# Display.net
KiCad netlist of a schematic drawn in Altium Designer
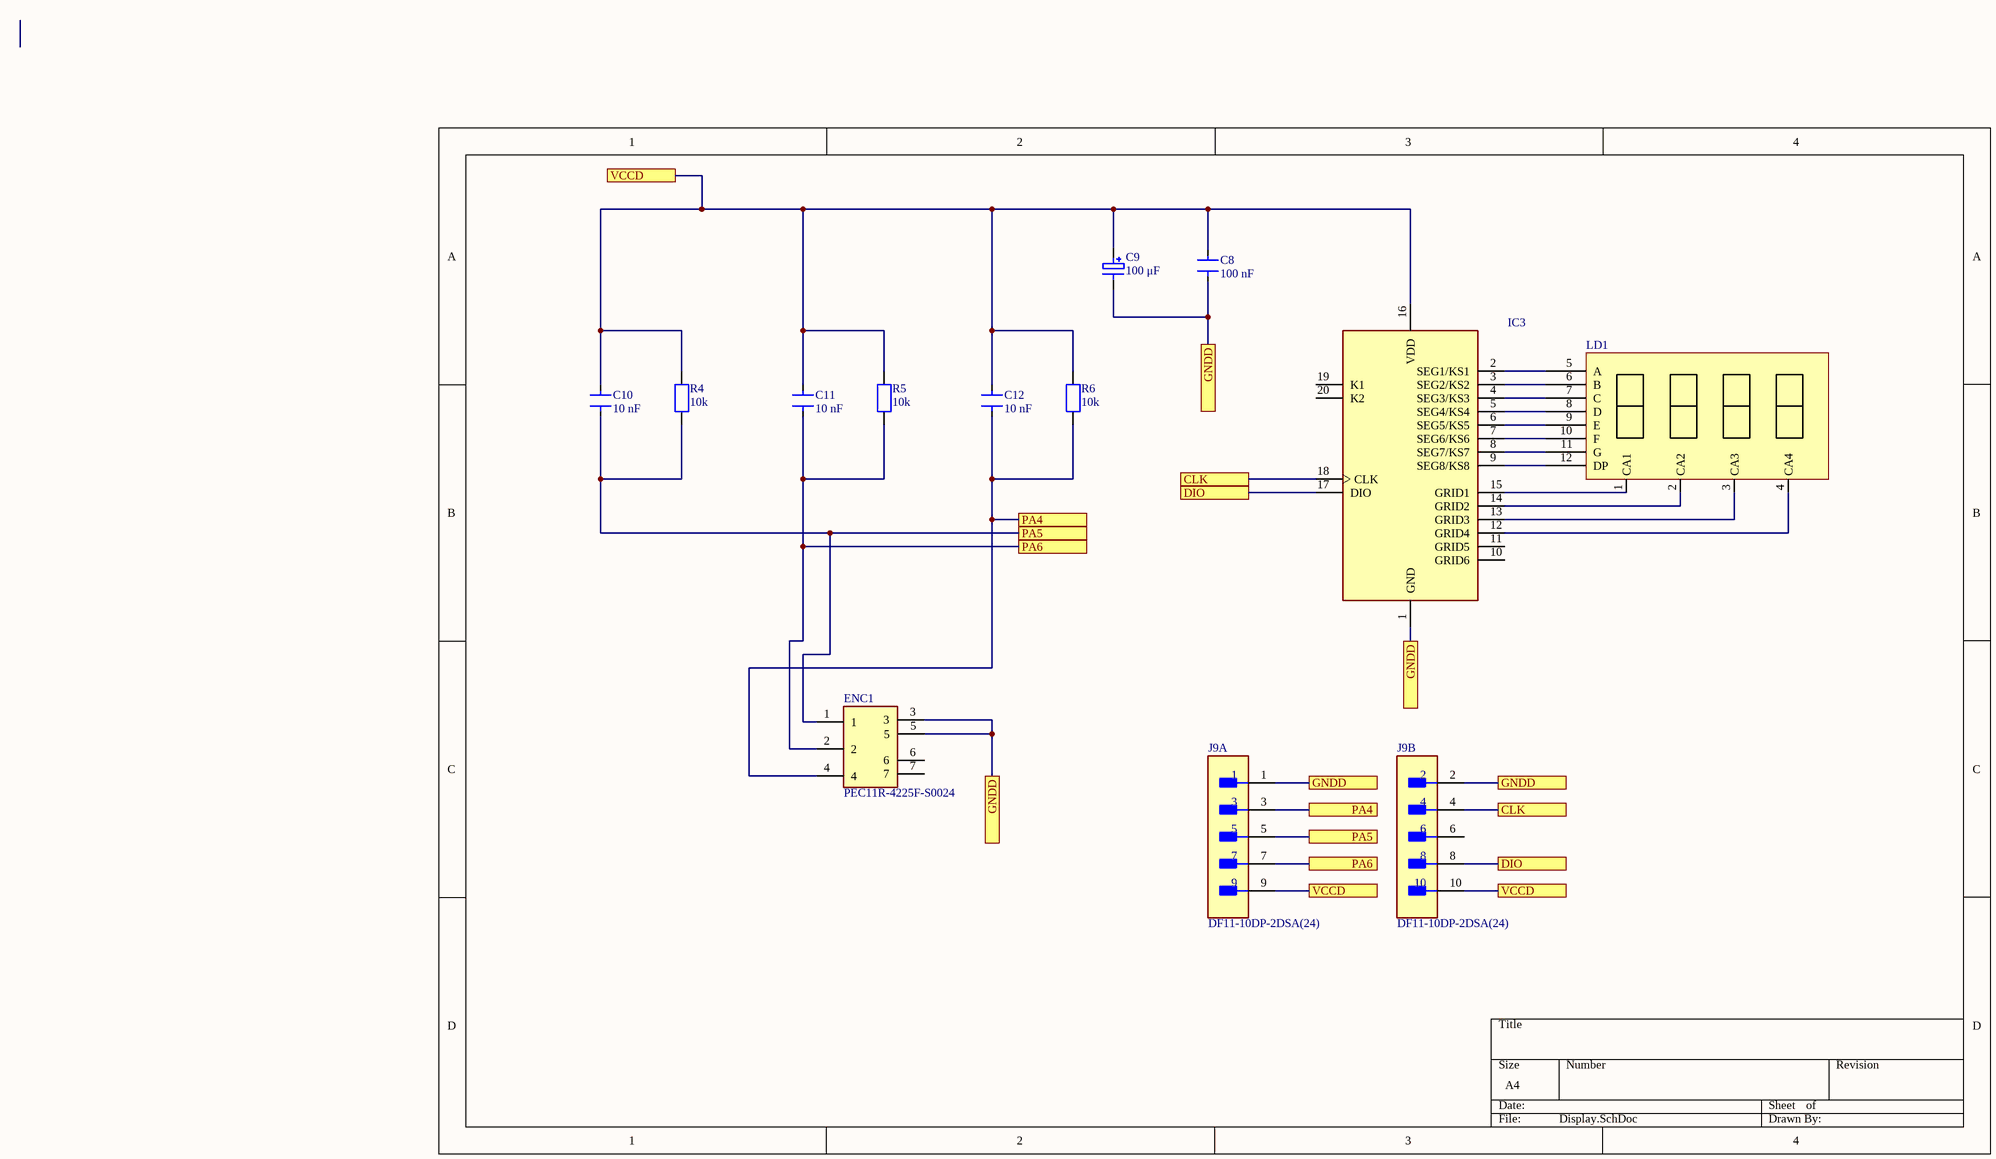
[diagram p0: Display.SchDoc]

(export (version "E")
  (design (tool "Eeschema 10.0.6"))
  (components
    (comp (ref "C8")
      (value "100 nF")
      (footprint "0805")
      (description "Chip Multilayer Ceramic Capacitors for General Purpose, 0805, 10uF, X5R, 15%, 10%, 25V")
      (fields (field (name "VOLTAGE") "25V") (field (name "TOLERANCE") "10%"))
      (libsource (lib "Soldeerstation") (part "Condensator 0805"))
    )
    (comp (ref "C9")
      (value "100 μF")
      (footprint "Elco 100uF 25V")
      (fields
        (field (name "PART NUMBER") "02015A270JAT2A")
        (field (name "MANUFACTURER") "AVX Interconnect / Elco")
      )
      (libsource (lib "Soldeerstation") (part "Condensator Elco"))
    )
    (comp (ref "C10")
      (value "10 nF")
      (footprint "0805")
      (description "Chip Multilayer Ceramic Capacitors for General Purpose, 0805, 10uF, X5R, 15%, 10%, 25V")
      (fields (field (name "VOLTAGE") "25V") (field (name "TOLERANCE") "10%"))
      (libsource (lib "Soldeerstation") (part "Condensator 0805"))
    )
    (comp (ref "C11")
      (value "10 nF")
      (footprint "0805")
      (description "Chip Multilayer Ceramic Capacitors for General Purpose, 0805, 10uF, X5R, 15%, 10%, 25V")
      (fields (field (name "VOLTAGE") "25V") (field (name "TOLERANCE") "10%"))
      (libsource (lib "Soldeerstation") (part "Condensator 0805"))
    )
    (comp (ref "C12")
      (value "10 nF")
      (footprint "0805")
      (description "Chip Multilayer Ceramic Capacitors for General Purpose, 0805, 10uF, X5R, 15%, 10%, 25V")
      (fields (field (name "VOLTAGE") "25V") (field (name "TOLERANCE") "10%"))
      (libsource (lib "Soldeerstation") (part "Condensator 0805"))
    )
    (comp (ref "ENC1")
      (value "PEC11R-4225F-S0024")
      (footprint "Encoder")
      (description "Undefined or Miscellaneous")
      (fields (field (name "MOUSER2 PART NUMBER") "652-PEC11R-4225F-S24"))
      (libsource (lib "Soldeerstation") (part "Encoder"))
    )
    (comp (ref "IC3")
      (value "TM1637")
      (footprint "TM1637")
      (description "LED Drive Control Special Circuit")
      (fields (field (name "MF") "Titan Micro Electronics"))
      (libsource (lib "Soldeerstation") (part "TM1637"))
    )
    (comp (ref "J9")
      (value "DF11-10DP-2DSA(24)")
      (footprint "FP-DF11-10DP-2DSA_24-MFG")
      (description "CONN HEADER VERT 10POS 2MM")
      (fields
        (field (name "OCTOPART") "https://octopart.com/df11-10dp-2dsa%2824%29-hirose-39521433")
        (field (name "MANUFACTURER") "Hirose")
      )
      (libsource (lib "Soldeerstation") (part "CMP-11610-000008-1"))
    )
    (comp (ref "LD1")
      (value "7segment")
      (footprint "7segment")
      (libsource (lib "Soldeerstation") (part "7segment"))
    )
    (comp (ref "R4")
      (value "10k")
      (footprint "Resistor")
      (description "Resistor")
      (fields (field (name "MANUFACTURER") "Vishay Dale") (field (name "PART NUMBER") "CRCW08050000Z0EA"))
      (libsource (lib "Soldeerstation") (part "Resistor"))
    )
    (comp (ref "R5")
      (value "10k")
      (footprint "Resistor")
      (description "Resistor")
      (fields (field (name "MANUFACTURER") "Vishay Dale") (field (name "PART NUMBER") "CRCW08050000Z0EA"))
      (libsource (lib "Soldeerstation") (part "Resistor"))
    )
    (comp (ref "R6")
      (value "10k")
      (footprint "Resistor")
      (description "Resistor")
      (fields (field (name "MANUFACTURER") "Vishay Dale") (field (name "PART NUMBER") "CRCW08050000Z0EA"))
      (libsource (lib "Soldeerstation") (part "Resistor"))
    )
  )
  (nets
    (net (code "1") (name "/CLK") (class "Default")
      (node (ref "IC3") (pin "18") (pinfunction "CLK_18") (pintype "passive"))
      (node (ref "J9") (pin "4") (pinfunction "4_4") (pintype "passive"))
    )
    (net (code "2") (name "/DIO") (class "Default")
      (node (ref "IC3") (pin "17") (pinfunction "DIO_17") (pintype "passive"))
      (node (ref "J9") (pin "8") (pinfunction "8_8") (pintype "passive"))
    )
    (net (code "3") (name "/GNDD") (class "Default")
      (node (ref "C8") (pin "1") (pinfunction "1_1") (pintype "passive"))
      (node (ref "C9") (pin "2") (pinfunction "2_2") (pintype "passive"))
      (node (ref "ENC1") (pin "3") (pinfunction "3_3") (pintype "passive"))
      (node (ref "ENC1") (pin "5") (pinfunction "5_5") (pintype "passive"))
      (node (ref "IC3") (pin "1") (pinfunction "GND_1") (pintype "power_in"))
      (node (ref "J9") (pin "1") (pinfunction "1_1") (pintype "passive"))
      (node (ref "J9") (pin "2") (pinfunction "2_2") (pintype "passive"))
    )
    (net (code "4") (name "/PA4") (class "Default")
      (node (ref "C12") (pin "1") (pinfunction "1_1") (pintype "passive"))
      (node (ref "ENC1") (pin "4") (pinfunction "4_4") (pintype "passive"))
      (node (ref "J9") (pin "3") (pinfunction "3_3") (pintype "passive"))
      (node (ref "R6") (pin "1") (pintype "passive"))
    )
    (net (code "5") (name "/PA5") (class "Default")
      (node (ref "C10") (pin "1") (pinfunction "1_1") (pintype "passive"))
      (node (ref "ENC1") (pin "1") (pinfunction "1_1") (pintype "passive"))
      (node (ref "J9") (pin "5") (pinfunction "5_5") (pintype "passive"))
      (node (ref "R4") (pin "1") (pintype "passive"))
    )
    (net (code "6") (name "/PA6") (class "Default")
      (node (ref "C11") (pin "1") (pinfunction "1_1") (pintype "passive"))
      (node (ref "ENC1") (pin "2") (pinfunction "2_2") (pintype "passive"))
      (node (ref "J9") (pin "7") (pinfunction "7_7") (pintype "passive"))
      (node (ref "R5") (pin "1") (pintype "passive"))
    )
    (net (code "7") (name "/VCCD") (class "Default")
      (node (ref "C10") (pin "2") (pinfunction "2_2") (pintype "passive"))
      (node (ref "C11") (pin "2") (pinfunction "2_2") (pintype "passive"))
      (node (ref "C12") (pin "2") (pinfunction "2_2") (pintype "passive"))
      (node (ref "C8") (pin "2") (pinfunction "2_2") (pintype "passive"))
      (node (ref "C9") (pin "1") (pinfunction "1_1") (pintype "passive"))
      (node (ref "IC3") (pin "16") (pinfunction "VDD_16") (pintype "power_in"))
      (node (ref "J9") (pin "10") (pinfunction "10_10") (pintype "passive"))
      (node (ref "J9") (pin "9") (pinfunction "9_9") (pintype "passive"))
      (node (ref "R4") (pin "2") (pinfunction "2_2") (pintype "passive"))
      (node (ref "R5") (pin "2") (pinfunction "2_2") (pintype "passive"))
      (node (ref "R6") (pin "2") (pinfunction "2_2") (pintype "passive"))
    )
    (net (code "8") (name "Net-(IC3-GRID1)") (class "Default")
      (node (ref "IC3") (pin "15") (pinfunction "GRID1_15") (pintype "passive"))
      (node (ref "LD1") (pin "1") (pinfunction "CA1_1") (pintype "power_in"))
    )
    (net (code "9") (name "Net-(IC3-GRID2)") (class "Default")
      (node (ref "IC3") (pin "14") (pinfunction "GRID2_14") (pintype "passive"))
      (node (ref "LD1") (pin "2") (pinfunction "CA2_2") (pintype "power_in"))
    )
    (net (code "10") (name "Net-(IC3-GRID3)") (class "Default")
      (node (ref "IC3") (pin "13") (pinfunction "GRID3_13") (pintype "passive"))
      (node (ref "LD1") (pin "3") (pinfunction "CA3_3") (pintype "power_in"))
    )
    (net (code "11") (name "Net-(IC3-GRID4)") (class "Default")
      (node (ref "IC3") (pin "12") (pinfunction "GRID4_12") (pintype "passive"))
      (node (ref "LD1") (pin "4") (pinfunction "CA4_4") (pintype "power_in"))
    )
    (net (code "12") (name "Net-(IC3-SEG1{slash}KS1)") (class "Default")
      (node (ref "IC3") (pin "2") (pinfunction "SEG1/KS1_2") (pintype "passive"))
      (node (ref "LD1") (pin "5") (pinfunction "A_5") (pintype "passive"))
    )
    (net (code "13") (name "Net-(IC3-SEG2{slash}KS2)") (class "Default")
      (node (ref "IC3") (pin "3") (pinfunction "SEG2/KS2_3") (pintype "passive"))
      (node (ref "LD1") (pin "6") (pinfunction "B_6") (pintype "passive"))
    )
    (net (code "14") (name "Net-(IC3-SEG3{slash}KS3)") (class "Default")
      (node (ref "IC3") (pin "4") (pinfunction "SEG3/KS3_4") (pintype "passive"))
      (node (ref "LD1") (pin "7") (pinfunction "C_7") (pintype "passive"))
    )
    (net (code "15") (name "Net-(IC3-SEG4{slash}KS4)") (class "Default")
      (node (ref "IC3") (pin "5") (pinfunction "SEG4/KS4_5") (pintype "passive"))
      (node (ref "LD1") (pin "8") (pinfunction "D_8") (pintype "passive"))
    )
    (net (code "16") (name "Net-(IC3-SEG5{slash}KS5)") (class "Default")
      (node (ref "IC3") (pin "6") (pinfunction "SEG5/KS5_6") (pintype "passive"))
      (node (ref "LD1") (pin "9") (pinfunction "E_9") (pintype "passive"))
    )
    (net (code "17") (name "Net-(IC3-SEG6{slash}KS6)") (class "Default")
      (node (ref "IC3") (pin "7") (pinfunction "SEG6/KS6_7") (pintype "passive"))
      (node (ref "LD1") (pin "10") (pinfunction "F_10") (pintype "passive"))
    )
    (net (code "18") (name "Net-(IC3-SEG7{slash}KS7)") (class "Default")
      (node (ref "IC3") (pin "8") (pinfunction "SEG7/KS7_8") (pintype "passive"))
      (node (ref "LD1") (pin "11") (pinfunction "G_11") (pintype "passive"))
    )
    (net (code "19") (name "Net-(IC3-SEG8{slash}KS8)") (class "Default")
      (node (ref "IC3") (pin "9") (pinfunction "SEG8/KS8_9") (pintype "passive"))
      (node (ref "LD1") (pin "12") (pinfunction "DP_12") (pintype "power_in"))
    )
    (net (code "20") (name "unconnected-(ENC1-Pad6)") (class "Default")
      (node (ref "ENC1") (pin "6") (pinfunction "6_6") (pintype "passive"))
    )
    (net (code "21") (name "unconnected-(ENC1-Pad7)") (class "Default")
      (node (ref "ENC1") (pin "7") (pinfunction "7_7") (pintype "passive"))
    )
    (net (code "22") (name "unconnected-(IC3-GRID5-Pad11)") (class "Default")
      (node (ref "IC3") (pin "11") (pinfunction "GRID5_11") (pintype "passive"))
    )
    (net (code "23") (name "unconnected-(IC3-GRID6-Pad10)") (class "Default")
      (node (ref "IC3") (pin "10") (pinfunction "GRID6_10") (pintype "passive"))
    )
    (net (code "24") (name "unconnected-(IC3-K1-Pad19)") (class "Default")
      (node (ref "IC3") (pin "19") (pinfunction "K1_19") (pintype "passive"))
    )
    (net (code "25") (name "unconnected-(IC3-K2-Pad20)") (class "Default")
      (node (ref "IC3") (pin "20") (pinfunction "K2_20") (pintype "passive"))
    )
    (net (code "26") (name "unconnected-(J9-Pad6)") (class "Default")
      (node (ref "J9") (pin "6") (pinfunction "6_6") (pintype "passive"))
    )
  )
)
